# power-v29.net
KiCad netlist of a schematic drawn in Altium Designer
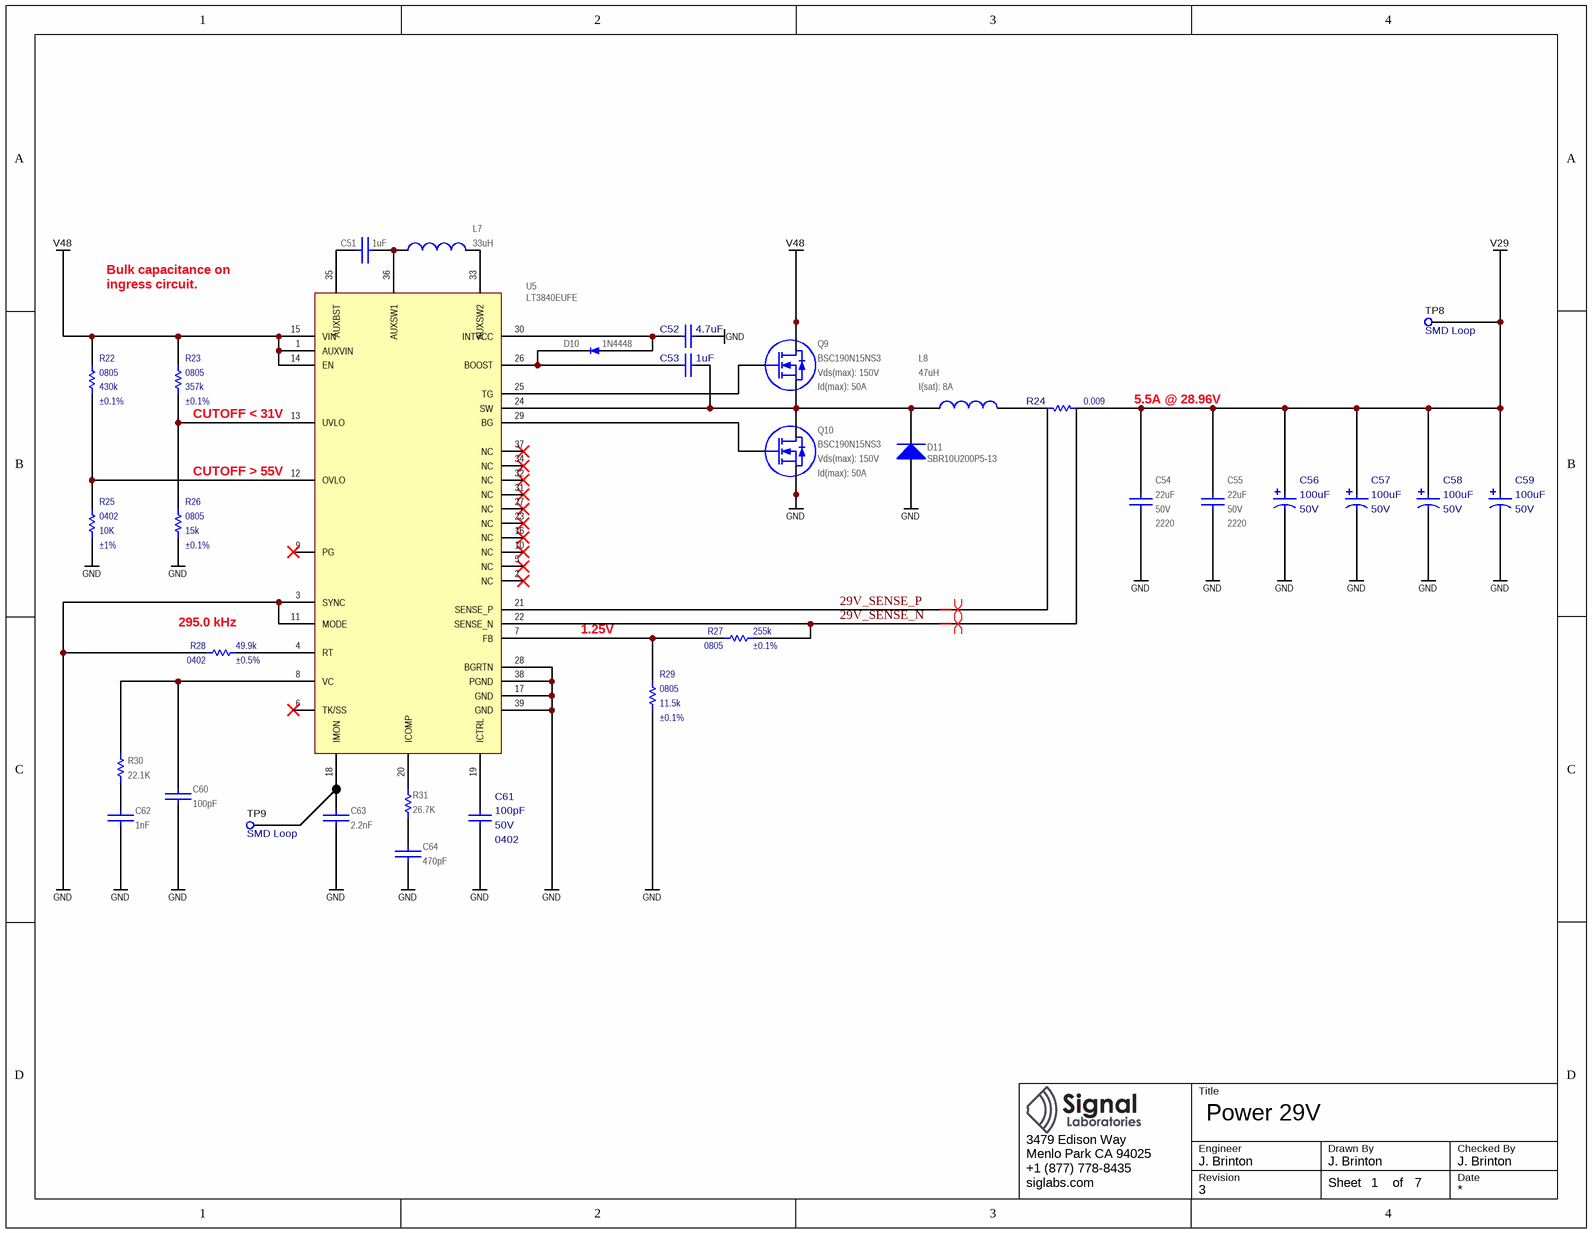
[diagram p0: power-v29.SchDoc]

(export (version "E")
  (design (tool "Eeschema 10.0.6"))
  (components
    (comp (ref "C51")
      (value "1uF")
      (footprint "CAPC100X50X55L25N")
      (description "Ceramic Capacitor 1uF ±10% 10V X5R 0402")
      (fields (field (name "MANUFACTURER") "Murata") (field (name "TOLERANCE") "±10%"))
      (libsource (lib "*") (part "CAP"))
    )
    (comp (ref "C52")
      (value "4.7uF")
      (footprint "CAPC160X80X90L20NA")
      (description "Ceramic Capacitor 4.7uF ±10% 25V X5R 0603")
      (fields (field (name "MANUFACTURER") "Samsung") (field (name "TOLERANCE") "±10%"))
      (libsource (lib "capacitors") (part "CAP"))
    )
    (comp (ref "C53")
      (value "1uF")
      (footprint "CAPC100X50X55L25N")
      (description "Ceramic Capacitor 1uF ±10% 10V X5R 0402")
      (fields (field (name "MANUFACTURER") "Murata") (field (name "TOLERANCE") "±10%"))
      (libsource (lib "capacitors") (part "CAP"))
    )
    (comp (ref "C54")
      (value "22uF")
      (footprint "CAPC600X500X500L160N")
      (description "Ceramic Capacitor 22uF ±20% 50V X7S Stacked")
      (fields
        (field (name "MANUFACTURER") "TDK")
        (field (name "TOLERANCE") "±20%")
        (field (name "VOLTAGE") "50V")
        (field (name "PACKAGE") "2220")
      )
      (libsource (lib "generic") (part "CAP"))
    )
    (comp (ref "C55")
      (value "22uF")
      (footprint "CAPC600X500X500L160N")
      (description "Ceramic Capacitor 22uF ±20% 50V X7S Stacked")
      (fields
        (field (name "MANUFACTURER") "TDK")
        (field (name "TOLERANCE") "±20%")
        (field (name "VOLTAGE") "50V")
        (field (name "PACKAGE") "2220")
      )
      (libsource (lib "generic") (part "CAP"))
    )
    (comp (ref "C56")
      (value "100uF")
      (footprint "panasonic-ecg:CAPAE660X800D700L260X65N")
      (description "Aluminum Electrolytic Capacitor 100uF ±20% 50V")
      (fields
        (field (name "MANUFACTURER") "Panasonic")
        (field (name "TOLERANCE") "±20%")
        (field (name "VOLTAGE") "50V")
      )
      (libsource (lib "avx") (part "CAP_POL"))
    )
    (comp (ref "C57")
      (value "100uF")
      (footprint "panasonic-ecg:CAPAE660X800D700L260X65N")
      (description "Aluminum Electrolytic Capacitor 100uF ±20% 50V")
      (fields
        (field (name "MANUFACTURER") "Panasonic")
        (field (name "TOLERANCE") "±20%")
        (field (name "VOLTAGE") "50V")
      )
      (libsource (lib "avx") (part "CAP_POL"))
    )
    (comp (ref "C58")
      (value "100uF")
      (footprint "panasonic-ecg:CAPAE660X800D700L260X65N")
      (description "Aluminum Electrolytic Capacitor 100uF ±20% 50V")
      (fields
        (field (name "MANUFACTURER") "Panasonic")
        (field (name "TOLERANCE") "±20%")
        (field (name "VOLTAGE") "50V")
      )
      (libsource (lib "avx") (part "CAP_POL"))
    )
    (comp (ref "C59")
      (value "100uF")
      (footprint "panasonic-ecg:CAPAE660X800D700L260X65N")
      (description "Aluminum Electrolytic Capacitor 100uF ±20% 50V")
      (fields
        (field (name "MANUFACTURER") "Panasonic")
        (field (name "TOLERANCE") "±20%")
        (field (name "VOLTAGE") "50V")
      )
      (libsource (lib "avx") (part "CAP_POL"))
    )
    (comp (ref "C60")
      (value "100pF")
      (footprint "CAPC100X50X55L25N")
      (description "Ceramic Capacitor 100pF ±1% 50V NP0 0402")
      (fields (field (name "MANUFACTURER") "Murata") (field (name "VOLTAGE") "50V"))
      (libsource (lib "*") (part "CAP"))
    )
    (comp (ref "C61")
      (value "100pF")
      (footprint "generic:CAPC100X50X55L25N")
      (description "Ceramic Capacitor 100pF ±10% 50V C0G 0402")
      (fields
        (field (name "MANUFACTURER") "Vishay")
        (field (name "TOLERANCE") "±10%")
        (field (name "PACKAGE") "0402")
        (field (name "VOLTAGE") "50V")
      )
      (libsource (lib "capacitors") (part "CAP"))
    )
    (comp (ref "C62")
      (value "1nF")
      (footprint "CAPC100X50X55L25N")
      (description "Ceramic Capacitor 1nF ±5% 50V NP0 0402")
      (fields (field (name "MANUFACTURER") "Murata") (field (name "VOLTAGE") "50V"))
      (libsource (lib "*") (part "CAP"))
    )
    (comp (ref "C63")
      (value "2.2nF")
      (footprint "CAPC100X50X55L25N")
      (description "Ceramic Capacitor 2.2nF ±5% 25V NP0 0402")
      (fields (field (name "MANUFACTURER") "Kemet") (field (name "TOLERANCE") "±5%"))
      (libsource (lib "*") (part "CAP"))
    )
    (comp (ref "C64")
      (value "470pF")
      (footprint "CAPC100X50X55L25N")
      (description "Ceramic Capacitor 470pF ±5% 50V X7R 0402")
      (fields (field (name "MANUFACTURER") "Murata") (field (name "VOLTAGE") "50V"))
      (libsource (lib "*") (part "CAP"))
    )
    (comp (ref "D10")
      (value "1N4448HWS-7-F")
      (footprint "diodes_inc:SOD323")
      (description "Schottky Diode 80V 250mA SOD323")
      (fields (field (name "MANUFACTURER") "Diodes Inc") (field (name "ALTERNATIVE P/N") "1N4448"))
      (libsource (lib "diodes_inc") (part "1N4448HWS-7-F"))
    )
    (comp (ref "D11")
      (value "SBR10U200P5-13")
      (footprint "DIODES_POWERDI5")
      (description "Schottky Diode 200V 10A SMD")
      (fields (field (name "MANUFACTURER") "Diodes Inc"))
      (libsource (lib "diodes_inc") (part "PDS5100H"))
    )
    (comp (ref "L7")
      (value "33uH")
      (footprint "coilcraft:ME3220")
      (description "Inductor 33uH ±10% 500mA SMD")
      (fields (field (name "MANUFACTURER") "Coilcraft") (field (name "TOLERANCE") "±10%"))
      (libsource (lib "CamBoard_Pico_70.19K") (part "COIL"))
    )
    (comp (ref "L8")
      (value "47uH")
      (footprint "cooper:HCM1A1707")
      (description "Inductor 47uH, 8A(sat), SMD")
      (fields
        (field (name "MANUFACTURER") "Eaton")
        (field (name "I(SAT)") "8A")
        (field (name "Comment") "HCM1A1707-470-R")
      )
      (libsource (lib "CamBoard_Pico_70.19K") (part "COIL"))
    )
    (comp (ref "Q9")
      (value "BSC190N15NS3")
      (footprint "TDSON-8")
      (description "MOSFET N-Channel Enhancement Mode")
      (fields
        (field (name "MANUFACTURER") "Infineon")
        (field (name "VDS(MAX)") "150V")
        (field (name "ID(MAX)") "50A")
      )
      (libsource (lib "infinion") (part "BSC190N15NS3"))
    )
    (comp (ref "Q10")
      (value "BSC190N15NS3")
      (footprint "TDSON-8")
      (description "MOSFET N-Channel Enhancement Mode")
      (fields
        (field (name "MANUFACTURER") "Infineon")
        (field (name "VDS(MAX)") "150V")
        (field (name "ID(MAX)") "50A")
      )
      (libsource (lib "infinion") (part "BSC190N15NS3"))
    )
    (comp (ref "R22")
      (value "430k")
      (footprint "RESC2012X70N")
      (description "Thin Film Resistor 430k +/-0.1% SMD 0805")
      (fields
        (field (name "TOLERANCE") "±0.1%")
        (field (name "MANUFACTURER") "Yageo")
        (field (name "PACKAGE") "0805")
        (field (name "Comment") "RT0805BRD07430KL")
      )
      (libsource (lib "generic") (part "RES"))
    )
    (comp (ref "R23")
      (value "357k")
      (footprint "RESC2012X70N")
      (description "Thin Film Resistor 357k +/-0.1% SMD 0805")
      (fields
        (field (name "TOLERANCE") "±0.1%")
        (field (name "MANUFACTURER") "Yageo")
        (field (name "PACKAGE") "0805")
        (field (name "Comment") "RT0805BRD07357KL")
      )
      (libsource (lib "generic") (part "RES"))
    )
    (comp (ref "R24")
      (value "0.009")
      (footprint "susumu:KRL3216T4")
      (description "Current Sense Resistor 9 mOhms +/-1% SMD 4-Terminal")
      (fields (field (name "TOLERANCE") "±1%") (field (name "MANUFACTURER") "Susumu"))
      (libsource (lib "susumu") (part "KRL3216T4A-M-R009-F"))
    )
    (comp (ref "R25")
      (value "10K")
      (footprint "RESC2012X70N")
      (description "Thick Film Resistor 10k ±1% 0.1W 50V 0402")
      (fields
        (field (name "TOLERANCE") "±1%")
        (field (name "MANUFACTURER") "Panasonic")
        (field (name "PACKAGE") "0402")
        (field (name "Comment") "ERJ-2RKF1002X")
      )
      (libsource (lib "generic") (part "RES"))
    )
    (comp (ref "R26")
      (value "15k")
      (footprint "RESC2012X70N")
      (description "Thin Film Resistor 15k +/-0.1% SMD 0805")
      (fields
        (field (name "TOLERANCE") "±0.1%")
        (field (name "MANUFACTURER") "Susumu")
        (field (name "PACKAGE") "0805")
        (field (name "Comment") "RG2012P-153-B-T5")
      )
      (libsource (lib "generic") (part "RES"))
    )
    (comp (ref "R27")
      (value "255k")
      (footprint "RESC2012X70N")
      (description "Thin Film Resistor 255k +/-0.1% SMD 0805")
      (fields
        (field (name "TOLERANCE") "±0.1%")
        (field (name "MANUFACTURER") "Vishay")
        (field (name "PACKAGE") "0805")
        (field (name "Comment") "PTN0805E2553BST1")
      )
      (libsource (lib "generic") (part "RES"))
    )
    (comp (ref "R28")
      (value "49.9k")
      (footprint "RESC1005X40N")
      (description "Thin Film Resistor 49.9k +/-0.5% SMD 0402")
      (fields
        (field (name "TOLERANCE") "±0.5%")
        (field (name "MANUFACTURER") "Susumu")
        (field (name "PACKAGE") "0402")
        (field (name "Comment") "RR0510P-4992-D")
      )
      (libsource (lib "generic") (part "RES"))
    )
    (comp (ref "R29")
      (value "11.5k")
      (footprint "RESC2012X70N")
      (description "Thin Film Resistor 11.5k +/-0.1% SMD 0805")
      (fields
        (field (name "TOLERANCE") "±0.1%")
        (field (name "MANUFACTURER") "Yageo")
        (field (name "PACKAGE") "0805")
        (field (name "Comment") "RT0805BRD0711K5L")
      )
      (libsource (lib "generic") (part "RES"))
    )
    (comp (ref "R30")
      (value "22.1K")
      (footprint "generic:RESC1005X40N")
      (description "Thick Film Resistor 22.1k ±1% 0402")
      (fields (field (name "MANUFACTURER") "Panasonic") (field (name "TOLERANCE") "±1%"))
      (libsource (lib "Graviton") (part "RES 0402"))
    )
    (comp (ref "R31")
      (value "26.7K")
      (footprint "generic:RESC1005X40N")
      (description "Thick Film Resistor 26.7k ±1% 0402")
      (fields (field (name "MANUFACTURER") "Panasonic") (field (name "TOLERANCE") "±1%"))
      (libsource (lib "Graviton") (part "RES 0402"))
    )
    (comp (ref "TP8")
      (value "5015")
      (footprint "keystone:5015")
      (description "Test Point SMD")
      (fields (field (name "MANUFACTURER") "Keystone") (field (name "NOTES") "SMD Loop"))
      (libsource (lib "generic") (part "TEST_POINT_SMD_50"))
    )
    (comp (ref "TP9")
      (value "5015")
      (footprint "keystone:5015")
      (description "Test Point SMD")
      (fields (field (name "MANUFACTURER") "Keystone") (field (name "NOTES") "SMD Loop"))
      (libsource (lib "generic") (part "TEST_POINT_SMD_50"))
    )
    (comp (ref "U5")
      (value "LT3840EUFE")
      (footprint "linear:QFN39P40_600X400X80L40X20T465X265N")
      (description "Synchronous Regulator Controller")
      (fields (field (name "MANUFACTURER") "Linear Technology"))
      (libsource (lib "linear") (part "LT3840EUFE"))
    )
  )
  (nets
    (net (code "1") (name "/29V_SENSE_N") (class "Default")
      (node (ref "R24") (pin "4") (pinfunction "4_4") (pintype "passive"))
      (node (ref "R27") (pin "1") (pinfunction "1_1") (pintype "passive"))
      (node (ref "U5") (pin "22") (pinfunction "SENSE_N_22") (pintype "passive"))
    )
    (net (code "2") (name "/29V_SENSE_P") (class "Default")
      (node (ref "R24") (pin "3") (pinfunction "3_3") (pintype "passive"))
      (node (ref "U5") (pin "21") (pinfunction "SENSE_P_21") (pintype "passive"))
    )
    (net (code "3") (name "GND") (class "Default")
      (node (ref "C52") (pin "2") (pinfunction "2_2") (pintype "passive"))
      (node (ref "C54") (pin "1") (pinfunction "1_1") (pintype "passive"))
      (node (ref "C55") (pin "1") (pinfunction "1_1") (pintype "passive"))
      (node (ref "C56") (pin "2") (pinfunction "2_2") (pintype "passive"))
      (node (ref "C57") (pin "2") (pinfunction "2_2") (pintype "passive"))
      (node (ref "C58") (pin "2") (pinfunction "2_2") (pintype "passive"))
      (node (ref "C59") (pin "2") (pinfunction "2_2") (pintype "passive"))
      (node (ref "C60") (pin "1") (pinfunction "1_1") (pintype "passive"))
      (node (ref "C61") (pin "2") (pinfunction "2_2") (pintype "passive"))
      (node (ref "C62") (pin "2") (pinfunction "2_2") (pintype "passive"))
      (node (ref "C63") (pin "2") (pinfunction "2_2") (pintype "passive"))
      (node (ref "C64") (pin "1") (pinfunction "1_1") (pintype "passive"))
      (node (ref "D11") (pin "A") (pinfunction "A_A") (pintype "power_in"))
      (node (ref "Q10") (pin "1") (pinfunction "S_1") (pintype "passive"))
      (node (ref "Q10") (pin "2") (pinfunction "S_2") (pintype "passive"))
      (node (ref "Q10") (pin "3") (pinfunction "S_3") (pintype "passive"))
      (node (ref "R25") (pin "1") (pinfunction "1_1") (pintype "passive"))
      (node (ref "R26") (pin "1") (pinfunction "1_1") (pintype "passive"))
      (node (ref "R28") (pin "2") (pinfunction "2_2") (pintype "passive"))
      (node (ref "R29") (pin "1") (pinfunction "1_1") (pintype "passive"))
      (node (ref "U5") (pin "11") (pinfunction "MODE_11") (pintype "passive"))
      (node (ref "U5") (pin "17") (pinfunction "GND_17") (pintype "passive"))
      (node (ref "U5") (pin "28") (pinfunction "BGRTN_28") (pintype "passive"))
      (node (ref "U5") (pin "3") (pinfunction "SYNC_3") (pintype "passive"))
      (node (ref "U5") (pin "38") (pinfunction "PGND_38") (pintype "passive"))
      (node (ref "U5") (pin "39") (pinfunction "GND_39") (pintype "passive"))
    )
    (net (code "4") (name "Net-(C62-Pad1)") (class "Default")
      (node (ref "C62") (pin "1") (pinfunction "1_1") (pintype "passive"))
      (node (ref "R30") (pin "1") (pinfunction "1_1") (pintype "passive"))
    )
    (net (code "5") (name "Net-(C64-Pad2)") (class "Default")
      (node (ref "C64") (pin "2") (pinfunction "2_2") (pintype "passive"))
      (node (ref "R31") (pin "2") (pinfunction "2_2") (pintype "passive"))
    )
    (net (code "6") (name "Net-(L8-Pad2)") (class "Default")
      (node (ref "L8") (pin "2") (pinfunction "2_2") (pintype "passive"))
      (node (ref "R24") (pin "1") (pinfunction "1_1") (pintype "passive"))
    )
    (net (code "7") (name "Net-(Q9-G)") (class "Default")
      (node (ref "Q9") (pin "4") (pinfunction "G_4") (pintype "passive"))
      (node (ref "U5") (pin "25") (pinfunction "TG_25") (pintype "passive"))
    )
    (net (code "8") (name "Net-(Q10-G)") (class "Default")
      (node (ref "Q10") (pin "4") (pinfunction "G_4") (pintype "passive"))
      (node (ref "U5") (pin "29") (pinfunction "BG_29") (pintype "passive"))
    )
    (net (code "9") (name "Net-(U5-AUXBST)") (class "Default")
      (node (ref "C51") (pin "2") (pinfunction "2_2") (pintype "passive"))
      (node (ref "U5") (pin "35") (pinfunction "AUXBST_35") (pintype "passive"))
    )
    (net (code "10") (name "Net-(U5-AUXSW1)") (class "Default")
      (node (ref "C51") (pin "1") (pinfunction "1_1") (pintype "passive"))
      (node (ref "L7") (pin "1") (pinfunction "1_1") (pintype "passive"))
      (node (ref "U5") (pin "36") (pinfunction "AUXSW1_36") (pintype "passive"))
    )
    (net (code "11") (name "Net-(U5-AUXSW2)") (class "Default")
      (node (ref "L7") (pin "2") (pinfunction "2_2") (pintype "passive"))
      (node (ref "U5") (pin "33") (pinfunction "AUXSW2_33") (pintype "passive"))
    )
    (net (code "12") (name "Net-(U5-BOOST)") (class "Default")
      (node (ref "C53") (pin "1") (pinfunction "1_1") (pintype "passive"))
      (node (ref "D10") (pin "K") (pinfunction "K_K") (pintype "passive"))
      (node (ref "U5") (pin "26") (pinfunction "BOOST_26") (pintype "passive"))
    )
    (net (code "13") (name "Net-(U5-FB)") (class "Default")
      (node (ref "R27") (pin "2") (pinfunction "2_2") (pintype "passive"))
      (node (ref "R29") (pin "2") (pinfunction "2_2") (pintype "passive"))
      (node (ref "U5") (pin "7") (pinfunction "FB_7") (pintype "passive"))
    )
    (net (code "14") (name "Net-(U5-ICOMP)") (class "Default")
      (node (ref "R31") (pin "1") (pinfunction "1_1") (pintype "passive"))
      (node (ref "U5") (pin "20") (pinfunction "ICOMP_20") (pintype "passive"))
    )
    (net (code "15") (name "Net-(U5-ICTRL)") (class "Default")
      (node (ref "C61") (pin "1") (pinfunction "1_1") (pintype "passive"))
      (node (ref "U5") (pin "19") (pinfunction "ICTRL_19") (pintype "passive"))
    )
    (net (code "16") (name "Net-(U5-IMON)") (class "Default")
      (node (ref "C63") (pin "1") (pinfunction "1_1") (pintype "passive"))
      (node (ref "TP9") (pin "1") (pinfunction "1_1") (pintype "passive"))
      (node (ref "U5") (pin "18") (pinfunction "IMON_18") (pintype "passive"))
    )
    (net (code "17") (name "Net-(U5-INTVCC)") (class "Default")
      (node (ref "C52") (pin "1") (pinfunction "1_1") (pintype "passive"))
      (node (ref "D10") (pin "A") (pinfunction "A_A") (pintype "passive"))
      (node (ref "U5") (pin "30") (pinfunction "INTVCC_30") (pintype "passive"))
    )
    (net (code "18") (name "Net-(U5-OVLO)") (class "Default")
      (node (ref "R22") (pin "1") (pinfunction "1_1") (pintype "passive"))
      (node (ref "R25") (pin "2") (pinfunction "2_2") (pintype "passive"))
      (node (ref "U5") (pin "12") (pinfunction "OVLO_12") (pintype "passive"))
    )
    (net (code "19") (name "Net-(U5-RT)") (class "Default")
      (node (ref "R28") (pin "1") (pinfunction "1_1") (pintype "passive"))
      (node (ref "U5") (pin "4") (pinfunction "RT_4") (pintype "passive"))
    )
    (net (code "20") (name "Net-(U5-SW)") (class "Default")
      (node (ref "C53") (pin "2") (pinfunction "2_2") (pintype "passive"))
      (node (ref "D11") (pin "K") (pinfunction "K_K") (pintype "passive"))
      (node (ref "L8") (pin "1") (pinfunction "1_1") (pintype "passive"))
      (node (ref "Q10") (pin "5") (pinfunction "D_5") (pintype "passive"))
      (node (ref "Q10") (pin "6") (pinfunction "D_6") (pintype "passive"))
      (node (ref "Q10") (pin "7") (pinfunction "D_7") (pintype "passive"))
      (node (ref "Q10") (pin "8") (pinfunction "D_8") (pintype "passive"))
      (node (ref "Q10") (pin "9") (pinfunction "D_9") (pintype "passive"))
      (node (ref "Q9") (pin "1") (pinfunction "S_1") (pintype "passive"))
      (node (ref "Q9") (pin "2") (pinfunction "S_2") (pintype "passive"))
      (node (ref "Q9") (pin "3") (pinfunction "S_3") (pintype "passive"))
      (node (ref "U5") (pin "24") (pinfunction "SW_24") (pintype "passive"))
    )
    (net (code "21") (name "Net-(U5-UVLO)") (class "Default")
      (node (ref "R23") (pin "1") (pinfunction "1_1") (pintype "passive"))
      (node (ref "R26") (pin "2") (pinfunction "2_2") (pintype "passive"))
      (node (ref "U5") (pin "13") (pinfunction "UVLO_13") (pintype "passive"))
    )
    (net (code "22") (name "Net-(U5-VC)") (class "Default")
      (node (ref "C60") (pin "2") (pinfunction "2_2") (pintype "passive"))
      (node (ref "R30") (pin "2") (pinfunction "2_2") (pintype "passive"))
      (node (ref "U5") (pin "8") (pinfunction "VC_8") (pintype "passive"))
    )
    (net (code "23") (name "V29") (class "Default")
      (node (ref "C54") (pin "2") (pinfunction "2_2") (pintype "passive"))
      (node (ref "C55") (pin "2") (pinfunction "2_2") (pintype "passive"))
      (node (ref "C56") (pin "1") (pinfunction "1_1") (pintype "passive"))
      (node (ref "C57") (pin "1") (pinfunction "1_1") (pintype "passive"))
      (node (ref "C58") (pin "1") (pinfunction "1_1") (pintype "passive"))
      (node (ref "C59") (pin "1") (pinfunction "1_1") (pintype "passive"))
      (node (ref "R24") (pin "2") (pinfunction "2_2") (pintype "passive"))
      (node (ref "TP8") (pin "1") (pinfunction "1_1") (pintype "passive"))
    )
    (net (code "24") (name "V48") (class "Default")
      (node (ref "Q9") (pin "5") (pinfunction "D_5") (pintype "passive"))
      (node (ref "Q9") (pin "6") (pinfunction "D_6") (pintype "passive"))
      (node (ref "Q9") (pin "7") (pinfunction "D_7") (pintype "passive"))
      (node (ref "Q9") (pin "8") (pinfunction "D_8") (pintype "passive"))
      (node (ref "Q9") (pin "9") (pinfunction "D_9") (pintype "passive"))
      (node (ref "R22") (pin "2") (pinfunction "2_2") (pintype "passive"))
      (node (ref "R23") (pin "2") (pinfunction "2_2") (pintype "passive"))
      (node (ref "U5") (pin "1") (pinfunction "AUXVIN_1") (pintype "passive"))
      (node (ref "U5") (pin "14") (pinfunction "EN_14") (pintype "passive"))
      (node (ref "U5") (pin "15") (pinfunction "VIN_15") (pintype "passive"))
    )
    (net (code "25") (name "unconnected-(U5-NC-Pad2)") (class "Default")
      (node (ref "U5") (pin "2") (pinfunction "NC_2") (pintype "passive+no_connect"))
    )
    (net (code "26") (name "unconnected-(U5-NC-Pad5)") (class "Default")
      (node (ref "U5") (pin "5") (pinfunction "NC_5") (pintype "passive+no_connect"))
    )
    (net (code "27") (name "unconnected-(U5-NC-Pad10)") (class "Default")
      (node (ref "U5") (pin "10") (pinfunction "NC_10") (pintype "passive+no_connect"))
    )
    (net (code "28") (name "unconnected-(U5-NC-Pad16)") (class "Default")
      (node (ref "U5") (pin "16") (pinfunction "NC_16") (pintype "passive+no_connect"))
    )
    (net (code "29") (name "unconnected-(U5-NC-Pad23)") (class "Default")
      (node (ref "U5") (pin "23") (pinfunction "NC_23") (pintype "passive+no_connect"))
    )
    (net (code "30") (name "unconnected-(U5-NC-Pad27)") (class "Default")
      (node (ref "U5") (pin "27") (pinfunction "NC_27") (pintype "passive+no_connect"))
    )
    (net (code "31") (name "unconnected-(U5-NC-Pad31)") (class "Default")
      (node (ref "U5") (pin "31") (pinfunction "NC_31") (pintype "passive+no_connect"))
    )
    (net (code "32") (name "unconnected-(U5-NC-Pad32)") (class "Default")
      (node (ref "U5") (pin "32") (pinfunction "NC_32") (pintype "passive+no_connect"))
    )
    (net (code "33") (name "unconnected-(U5-NC-Pad34)") (class "Default")
      (node (ref "U5") (pin "34") (pinfunction "NC_34") (pintype "passive+no_connect"))
    )
    (net (code "34") (name "unconnected-(U5-NC-Pad37)") (class "Default")
      (node (ref "U5") (pin "37") (pinfunction "NC_37") (pintype "passive+no_connect"))
    )
    (net (code "35") (name "unconnected-(U5-PG-Pad9)") (class "Default")
      (node (ref "U5") (pin "9") (pinfunction "PG_9") (pintype "passive+no_connect"))
    )
    (net (code "36") (name "unconnected-(U5-TK{slash}SS-Pad6)") (class "Default")
      (node (ref "U5") (pin "6") (pinfunction "TK/SS_6") (pintype "passive+no_connect"))
    )
  )
)
